# RF_HACK_shematic.net
KiCad netlist of a schematic drawn in Altium Designer
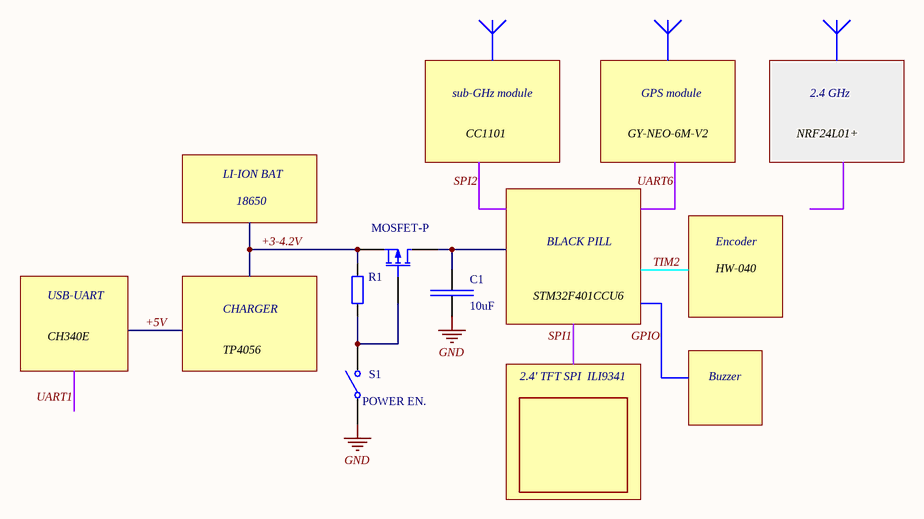
[diagram p0: RF_HACK_shematic.SchDoc]

(export (version "E")
  (design (tool "Eeschema 10.0.6"))
  (components
    (comp (ref "C1")
      (value "10uF")
      (footprint "CAPC1608X90")
      (description "Керамический ЧИП-конденсатор 0603 X5R 10мкФ ±20% 25В")
      (libsource (lib "GameConsil") (part "CC0603MRX5R8BB106"))
    )
    (comp (ref "Q1")
      (value "MOSFET-P")
      (footprint "E3")
      (description "P-Channel MOSFET")
      (fields (field (name "PUBLISHER") "Altium Limited"))
      (libsource (lib "Miscellaneous Devices") (part "MOSFET-P"))
    )
    (comp (ref "R1")
      (value "4.7K")
      (footprint "AXIAL-0.4")
      (description "Resistor")
      (fields (field (name "PUBLISHER") "Altium Limited"))
      (libsource (lib "Miscellaneous Devices") (part "Res2"))
    )
    (comp (ref "S1")
      (value "POWER EN.")
      (footprint "SPST-2")
      (description "Single-Pole, Single-Throw Switch")
      (fields (field (name "PUBLISHER") "Altium Limited"))
      (libsource (lib "Miscellaneous Devices") (part "SW-SPST"))
    )
  )
  (nets
    (net (code "1") (name "/+3-4.2V") (class "Default")
      (node (ref "Q1") (pin "3") (pinfunction "S_3") (pintype "passive"))
      (node (ref "R1") (pin "2") (pinfunction "2_2") (pintype "passive"))
    )
    (net (code "9") (name "GND") (class "Default")
      (node (ref "C1") (pin "1") (pinfunction "1_1") (pintype "passive"))
      (node (ref "S1") (pin "1") (pinfunction "COMMON_1") (pintype "passive"))
    )
    (net (code "10") (name "Net-(Q1-D)") (class "Default")
      (node (ref "C1") (pin "2") (pinfunction "2_2") (pintype "passive"))
      (node (ref "Q1") (pin "1") (pinfunction "D_1") (pintype "passive"))
    )
    (net (code "11") (name "Net-(Q1-G)") (class "Default")
      (node (ref "Q1") (pin "2") (pinfunction "G_2") (pintype "passive"))
      (node (ref "R1") (pin "1") (pinfunction "1_1") (pintype "passive"))
      (node (ref "S1") (pin "2") (pinfunction "NO_2") (pintype "passive"))
    )
  )
)
